# 1-Schematic_EspRosNodeCAN.net
KiCad netlist of a schematic drawn in EasyEDA
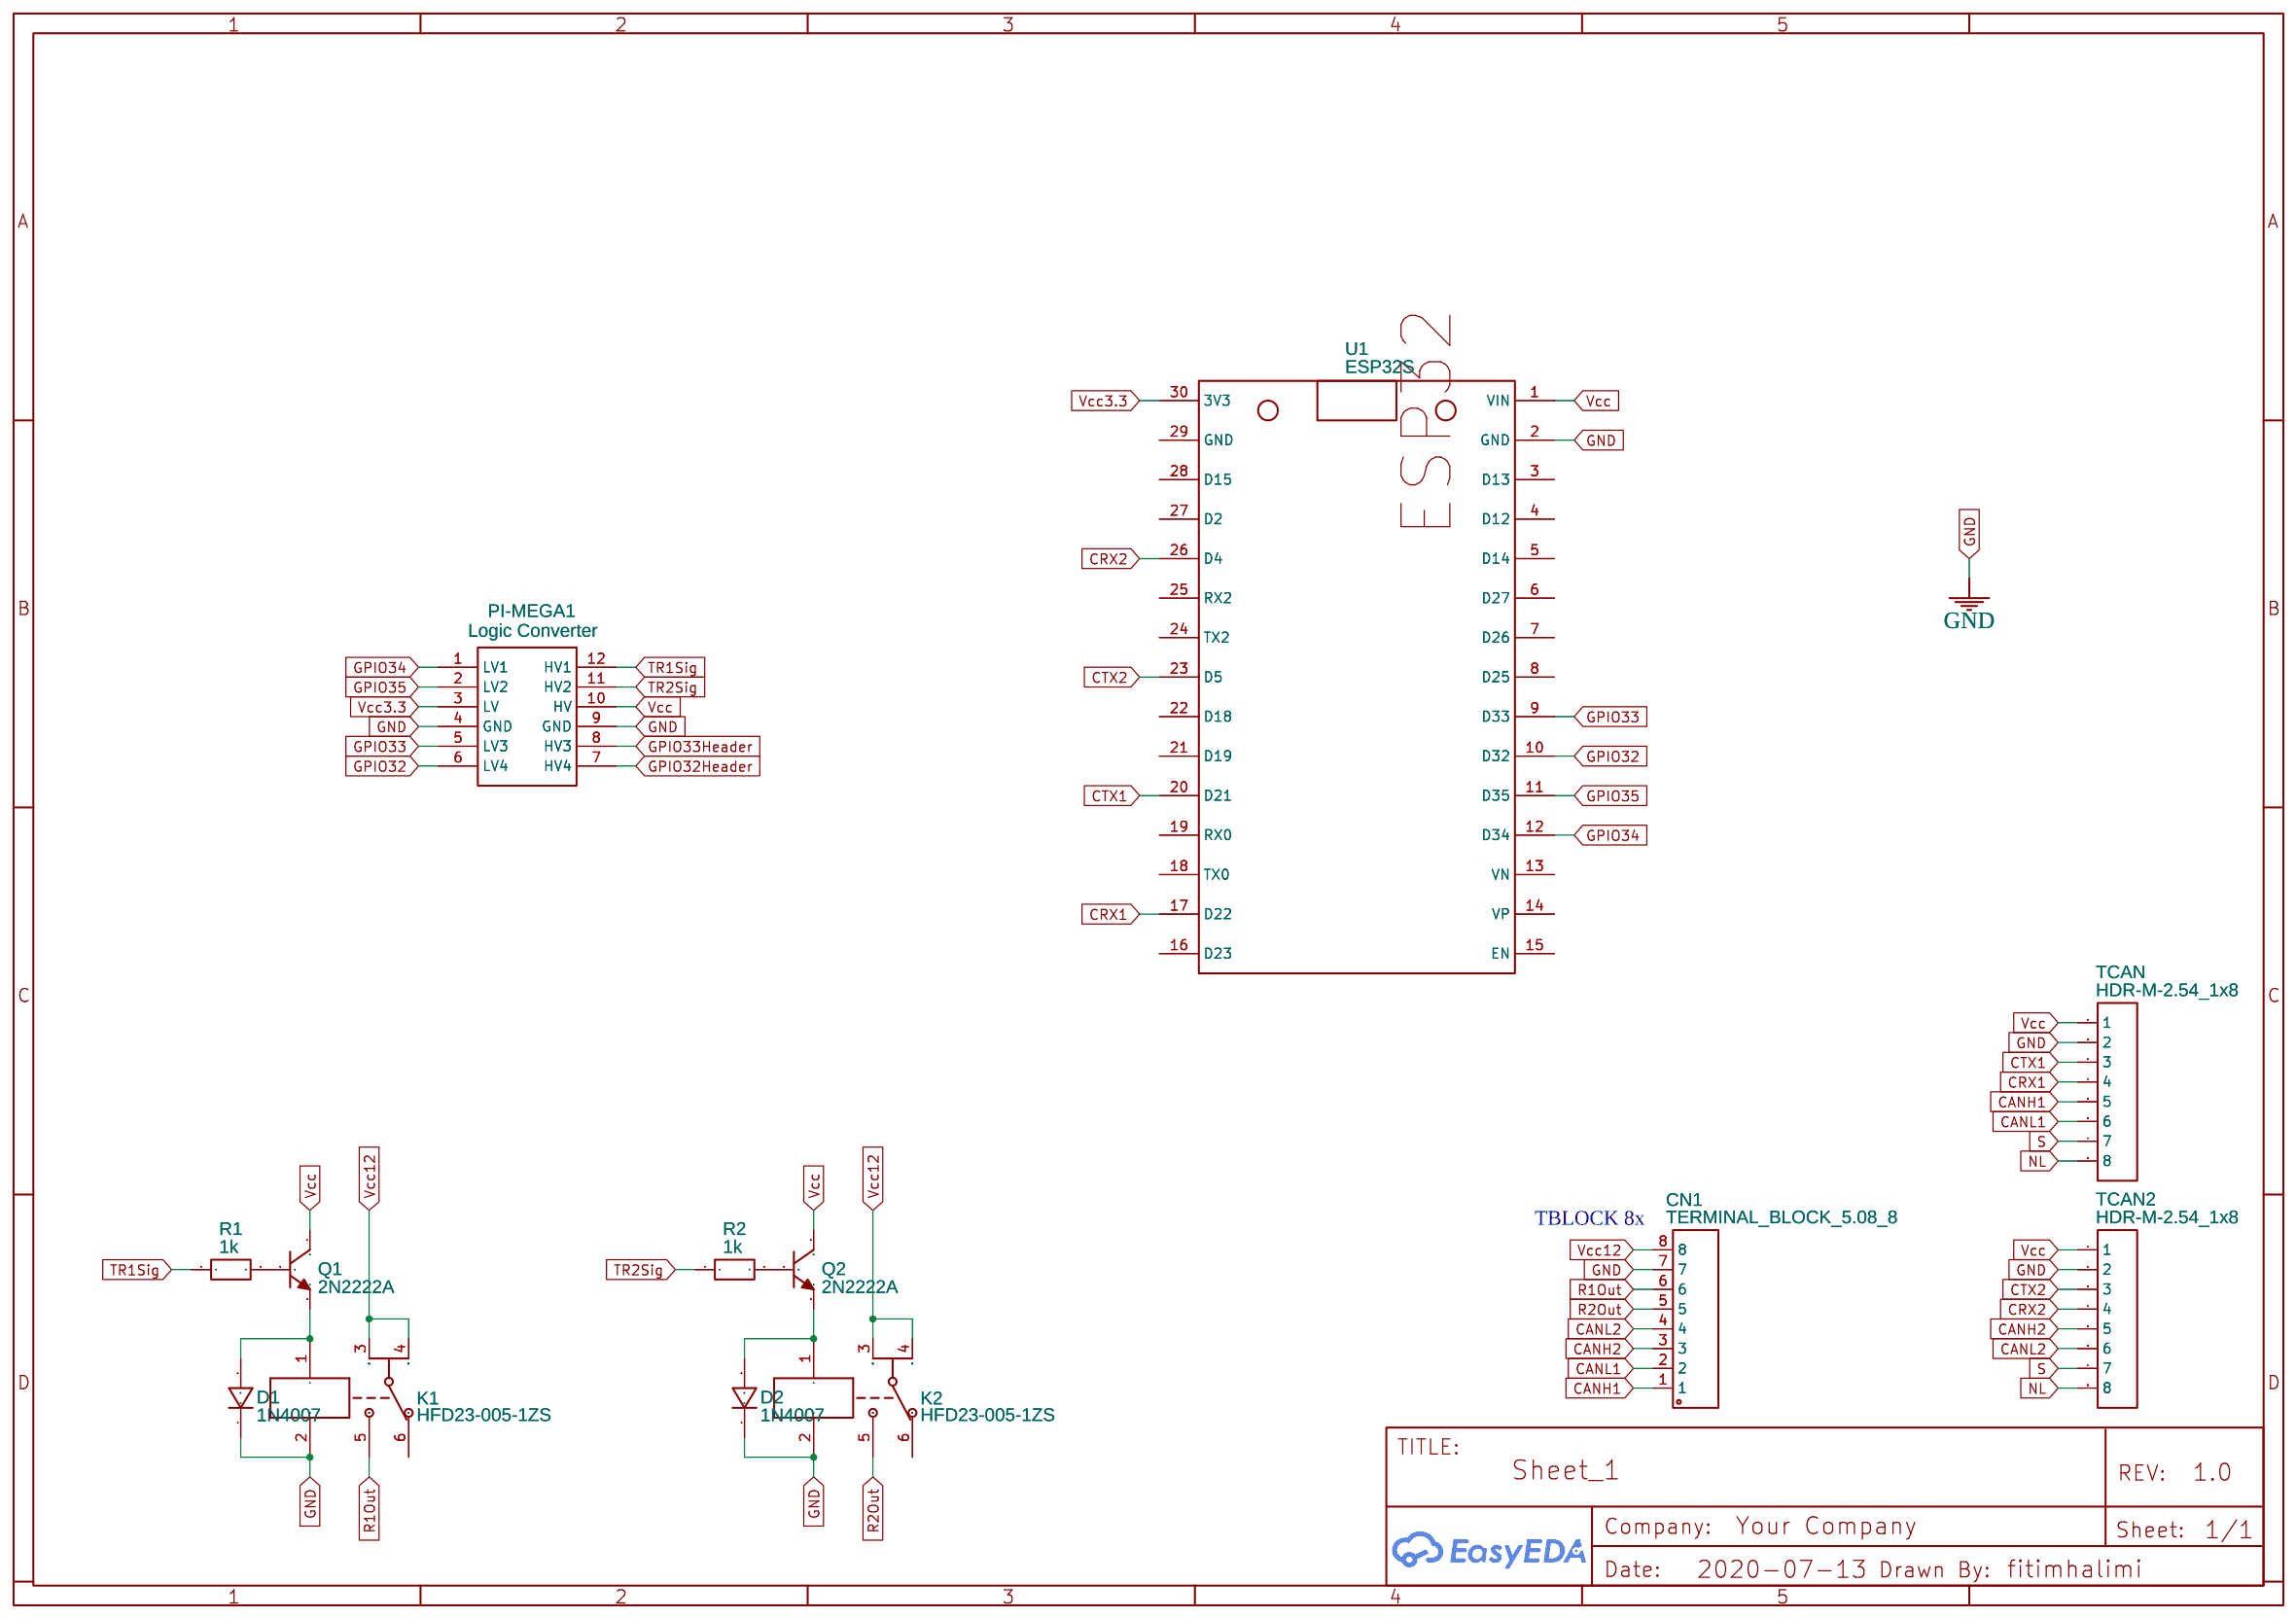
[diagram p0: schematic sheet]

(export (version "E")
  (design (tool "Eeschema 10.0.6"))
  (components
    (comp (ref "CN1") (value "TERMINAL_BLOCK_5.08_8") (libsource (lib "") (part "TERMINAL_BLOCK_5.08_8")))
    (comp (ref "D1")
      (value "1N4007")
      (fields (field (name "BOM_Supplier Part") "C106903"))
      (libsource (lib "") (part "1N4007"))
    )
    (comp (ref "D2")
      (value "1N4007")
      (fields (field (name "BOM_Supplier Part") "C106903"))
      (libsource (lib "") (part "1N4007"))
    )
    (comp (ref "K1")
      (value "HFD23-005-1ZS")
      (fields (field (name "BOM_Supplier Part") "C64002"))
      (libsource (lib "") (part "HFD23-005-1ZS"))
    )
    (comp (ref "K2")
      (value "HFD23-005-1ZS")
      (fields (field (name "BOM_Supplier Part") "C64002"))
      (libsource (lib "") (part "HFD23-005-1ZS"))
    )
    (comp (ref "PI-MEGA1")
      (value "Logic Converter")
      (fields (field (name "BOM_Manufacturer Part") "New SchematicLib"))
      (libsource (lib "") (part "4 Way Bi-Directional Logic Level Converter"))
    )
    (comp (ref "Q1")
      (value "2N2222A")
      (fields (field (name "BOM_Supplier Part") "C358533"))
      (libsource (lib "") (part "2N2222A"))
    )
    (comp (ref "Q2")
      (value "2N2222A")
      (fields (field (name "BOM_Supplier Part") "C358533"))
      (libsource (lib "") (part "2N2222A"))
    )
    (comp (ref "R1") (value "1k") (libsource (lib "") (part "R_AXIAL-0.4_EU")))
    (comp (ref "R2") (value "1k") (libsource (lib "") (part "R_AXIAL-0.4_EU")))
    (comp (ref "TCAN")
      (value "HDR-M-2.54_1x8")
      (fields (field (name "BOM_Supplier Part") "C190820"))
      (libsource (lib "") (part "HDR-M-2.54_1x8"))
    )
    (comp (ref "TCAN2")
      (value "HDR-M-2.54_1x8")
      (fields (field (name "BOM_Supplier Part") "C190820"))
      (libsource (lib "") (part "HDR-M-2.54_1x8"))
    )
    (comp (ref "U1")
      (value "ESP32S")
      (fields (field (name "BOM_Manufacturer Part") "New SchematicLib"))
      (libsource (lib "") (part "ESP32S"))
    )
  )
  (nets
    (net (code "1") (name "CANH1") (class "Default")
      (node (ref "CN1") (pin "1") (pinfunction "1_1") (pintype "unspecified"))
      (node (ref "TCAN") (pin "5") (pinfunction "5_5") (pintype "unspecified"))
    )
    (net (code "2") (name "CANH2") (class "Default")
      (node (ref "CN1") (pin "3") (pinfunction "3_3") (pintype "unspecified"))
      (node (ref "TCAN2") (pin "5") (pinfunction "5_5") (pintype "unspecified"))
    )
    (net (code "3") (name "CANL1") (class "Default")
      (node (ref "CN1") (pin "2") (pinfunction "2_2") (pintype "unspecified"))
      (node (ref "TCAN") (pin "6") (pinfunction "6_6") (pintype "unspecified"))
    )
    (net (code "4") (name "CANL2") (class "Default")
      (node (ref "CN1") (pin "4") (pinfunction "4_4") (pintype "unspecified"))
      (node (ref "TCAN2") (pin "6") (pinfunction "6_6") (pintype "unspecified"))
    )
    (net (code "5") (name "CRX1") (class "Default")
      (node (ref "TCAN") (pin "4") (pinfunction "4_4") (pintype "unspecified"))
      (node (ref "U1") (pin "17") (pinfunction "D22_17") (pintype "unspecified"))
    )
    (net (code "6") (name "CRX2") (class "Default")
      (node (ref "TCAN2") (pin "4") (pinfunction "4_4") (pintype "unspecified"))
      (node (ref "U1") (pin "26") (pinfunction "D4_26") (pintype "unspecified"))
    )
    (net (code "7") (name "CTX1") (class "Default")
      (node (ref "TCAN") (pin "3") (pinfunction "3_3") (pintype "unspecified"))
      (node (ref "U1") (pin "20") (pinfunction "D21_20") (pintype "unspecified"))
    )
    (net (code "8") (name "CTX2") (class "Default")
      (node (ref "TCAN2") (pin "3") (pinfunction "3_3") (pintype "unspecified"))
      (node (ref "U1") (pin "23") (pinfunction "D5_23") (pintype "unspecified"))
    )
    (net (code "9") (name "GND") (class "Default")
      (node (ref "CN1") (pin "7") (pinfunction "7_7") (pintype "unspecified"))
      (node (ref "D1") (pin "1") (pinfunction "1_1") (pintype "unspecified"))
      (node (ref "D2") (pin "1") (pinfunction "1_1") (pintype "unspecified"))
      (node (ref "K1") (pin "2") (pinfunction "2_2") (pintype "unspecified"))
      (node (ref "K2") (pin "2") (pinfunction "2_2") (pintype "unspecified"))
      (node (ref "PI-MEGA1") (pin "4") (pinfunction "GND_4") (pintype "unspecified"))
      (node (ref "PI-MEGA1") (pin "9") (pinfunction "GND_9") (pintype "unspecified"))
      (node (ref "TCAN") (pin "2") (pinfunction "2_2") (pintype "unspecified"))
      (node (ref "TCAN2") (pin "2") (pinfunction "2_2") (pintype "unspecified"))
      (node (ref "U1") (pin "2") (pinfunction "GND_2") (pintype "unspecified"))
    )
    (net (code "10") (name "GPIO32") (class "Default")
      (node (ref "PI-MEGA1") (pin "6") (pinfunction "LV4_6") (pintype "unspecified"))
      (node (ref "U1") (pin "10") (pinfunction "D32_10") (pintype "unspecified"))
    )
    (net (code "11") (name "GPIO32Header") (class "Default")
      (node (ref "PI-MEGA1") (pin "7") (pinfunction "HV4_7") (pintype "unspecified"))
    )
    (net (code "12") (name "GPIO33") (class "Default")
      (node (ref "PI-MEGA1") (pin "5") (pinfunction "LV3_5") (pintype "unspecified"))
      (node (ref "U1") (pin "9") (pinfunction "D33_9") (pintype "unspecified"))
    )
    (net (code "13") (name "GPIO33Header") (class "Default")
      (node (ref "PI-MEGA1") (pin "8") (pinfunction "HV3_8") (pintype "unspecified"))
    )
    (net (code "14") (name "GPIO34") (class "Default")
      (node (ref "PI-MEGA1") (pin "1") (pinfunction "LV1_1") (pintype "unspecified"))
      (node (ref "U1") (pin "12") (pinfunction "D34_12") (pintype "unspecified"))
    )
    (net (code "15") (name "GPIO35") (class "Default")
      (node (ref "PI-MEGA1") (pin "2") (pinfunction "LV2_2") (pintype "unspecified"))
      (node (ref "U1") (pin "11") (pinfunction "D35_11") (pintype "unspecified"))
    )
    (net (code "16") (name "NL") (class "Default")
      (node (ref "TCAN") (pin "8") (pinfunction "8_8") (pintype "unspecified"))
      (node (ref "TCAN2") (pin "8") (pinfunction "8_8") (pintype "unspecified"))
    )
    (net (code "17") (name "Net-(Q1-B)") (class "Default")
      (node (ref "Q1") (pin "2") (pinfunction "B_2") (pintype "unspecified"))
      (node (ref "R1") (pin "2") (pinfunction "2_2") (pintype "unspecified"))
    )
    (net (code "18") (name "Net-(Q1-E)") (class "Default")
      (node (ref "D1") (pin "2") (pinfunction "2_2") (pintype "unspecified"))
      (node (ref "K1") (pin "1") (pinfunction "1_1") (pintype "unspecified"))
      (node (ref "Q1") (pin "3") (pinfunction "E_3") (pintype "unspecified"))
    )
    (net (code "19") (name "Net-(Q2-B)") (class "Default")
      (node (ref "Q2") (pin "2") (pinfunction "B_2") (pintype "unspecified"))
      (node (ref "R2") (pin "2") (pinfunction "2_2") (pintype "unspecified"))
    )
    (net (code "20") (name "Net-(Q2-E)") (class "Default")
      (node (ref "D2") (pin "2") (pinfunction "2_2") (pintype "unspecified"))
      (node (ref "K2") (pin "1") (pinfunction "1_1") (pintype "unspecified"))
      (node (ref "Q2") (pin "3") (pinfunction "E_3") (pintype "unspecified"))
    )
    (net (code "21") (name "R1Out") (class "Default")
      (node (ref "CN1") (pin "6") (pinfunction "6_6") (pintype "unspecified"))
      (node (ref "K1") (pin "5") (pinfunction "NO_5") (pintype "unspecified"))
    )
    (net (code "22") (name "R2Out") (class "Default")
      (node (ref "CN1") (pin "5") (pinfunction "5_5") (pintype "unspecified"))
      (node (ref "K2") (pin "5") (pinfunction "NO_5") (pintype "unspecified"))
    )
    (net (code "23") (name "S") (class "Default")
      (node (ref "TCAN") (pin "7") (pinfunction "7_7") (pintype "unspecified"))
      (node (ref "TCAN2") (pin "7") (pinfunction "7_7") (pintype "unspecified"))
    )
    (net (code "24") (name "TR1Sig") (class "Default")
      (node (ref "PI-MEGA1") (pin "12") (pinfunction "HV1_12") (pintype "unspecified"))
      (node (ref "R1") (pin "1") (pinfunction "1_1") (pintype "unspecified"))
    )
    (net (code "25") (name "TR2Sig") (class "Default")
      (node (ref "PI-MEGA1") (pin "11") (pinfunction "HV2_11") (pintype "unspecified"))
      (node (ref "R2") (pin "1") (pinfunction "1_1") (pintype "unspecified"))
    )
    (net (code "26") (name "Vcc") (class "Default")
      (node (ref "PI-MEGA1") (pin "10") (pinfunction "HV_10") (pintype "unspecified"))
      (node (ref "Q1") (pin "1") (pinfunction "C_1") (pintype "unspecified"))
      (node (ref "Q2") (pin "1") (pinfunction "C_1") (pintype "unspecified"))
      (node (ref "TCAN") (pin "1") (pinfunction "1_1") (pintype "unspecified"))
      (node (ref "TCAN2") (pin "1") (pinfunction "1_1") (pintype "unspecified"))
      (node (ref "U1") (pin "1") (pinfunction "VIN_1") (pintype "unspecified"))
    )
    (net (code "27") (name "Vcc3.3") (class "Default")
      (node (ref "PI-MEGA1") (pin "3") (pinfunction "LV_3") (pintype "unspecified"))
      (node (ref "U1") (pin "30") (pinfunction "3V3_30") (pintype "unspecified"))
    )
    (net (code "28") (name "Vcc12") (class "Default")
      (node (ref "CN1") (pin "8") (pinfunction "8_8") (pintype "unspecified"))
      (node (ref "K1") (pin "3") (pinfunction "COM_3") (pintype "unspecified"))
      (node (ref "K1") (pin "4") (pinfunction "COM_4") (pintype "unspecified"))
      (node (ref "K2") (pin "3") (pinfunction "COM_3") (pintype "unspecified"))
      (node (ref "K2") (pin "4") (pinfunction "COM_4") (pintype "unspecified"))
    )
    (net (code "29") (name "unconnected-(K1-NC-Pad6)") (class "Default")
      (node (ref "K1") (pin "6") (pinfunction "NC_6") (pintype "unspecified"))
    )
    (net (code "30") (name "unconnected-(K2-NC-Pad6)") (class "Default")
      (node (ref "K2") (pin "6") (pinfunction "NC_6") (pintype "unspecified"))
    )
    (net (code "31") (name "unconnected-(U1-D2-Pad27)") (class "Default")
      (node (ref "U1") (pin "27") (pinfunction "D2_27") (pintype "unspecified"))
    )
    (net (code "32") (name "unconnected-(U1-D12-Pad4)") (class "Default")
      (node (ref "U1") (pin "4") (pinfunction "D12_4") (pintype "unspecified"))
    )
    (net (code "33") (name "unconnected-(U1-D13-Pad3)") (class "Default")
      (node (ref "U1") (pin "3") (pinfunction "D13_3") (pintype "unspecified"))
    )
    (net (code "34") (name "unconnected-(U1-D14-Pad5)") (class "Default")
      (node (ref "U1") (pin "5") (pinfunction "D14_5") (pintype "unspecified"))
    )
    (net (code "35") (name "unconnected-(U1-D15-Pad28)") (class "Default")
      (node (ref "U1") (pin "28") (pinfunction "D15_28") (pintype "unspecified"))
    )
    (net (code "36") (name "unconnected-(U1-D18-Pad22)") (class "Default")
      (node (ref "U1") (pin "22") (pinfunction "D18_22") (pintype "unspecified"))
    )
    (net (code "37") (name "unconnected-(U1-D19-Pad21)") (class "Default")
      (node (ref "U1") (pin "21") (pinfunction "D19_21") (pintype "unspecified"))
    )
    (net (code "38") (name "unconnected-(U1-D23-Pad16)") (class "Default")
      (node (ref "U1") (pin "16") (pinfunction "D23_16") (pintype "unspecified"))
    )
    (net (code "39") (name "unconnected-(U1-D25-Pad8)") (class "Default")
      (node (ref "U1") (pin "8") (pinfunction "D25_8") (pintype "unspecified"))
    )
    (net (code "40") (name "unconnected-(U1-D26-Pad7)") (class "Default")
      (node (ref "U1") (pin "7") (pinfunction "D26_7") (pintype "unspecified"))
    )
    (net (code "41") (name "unconnected-(U1-D27-Pad6)") (class "Default")
      (node (ref "U1") (pin "6") (pinfunction "D27_6") (pintype "unspecified"))
    )
    (net (code "42") (name "unconnected-(U1-EN-Pad15)") (class "Default")
      (node (ref "U1") (pin "15") (pinfunction "EN_15") (pintype "unspecified"))
    )
    (net (code "43") (name "unconnected-(U1-GND-Pad29)") (class "Default")
      (node (ref "U1") (pin "29") (pinfunction "GND_29") (pintype "unspecified"))
    )
    (net (code "44") (name "unconnected-(U1-RX0-Pad19)") (class "Default")
      (node (ref "U1") (pin "19") (pinfunction "RX0_19") (pintype "unspecified"))
    )
    (net (code "45") (name "unconnected-(U1-RX2-Pad25)") (class "Default")
      (node (ref "U1") (pin "25") (pinfunction "RX2_25") (pintype "unspecified"))
    )
    (net (code "46") (name "unconnected-(U1-TX0-Pad18)") (class "Default")
      (node (ref "U1") (pin "18") (pinfunction "TX0_18") (pintype "unspecified"))
    )
    (net (code "47") (name "unconnected-(U1-TX2-Pad24)") (class "Default")
      (node (ref "U1") (pin "24") (pinfunction "TX2_24") (pintype "unspecified"))
    )
    (net (code "48") (name "unconnected-(U1-VN-Pad13)") (class "Default")
      (node (ref "U1") (pin "13") (pinfunction "VN_13") (pintype "unspecified"))
    )
    (net (code "49") (name "unconnected-(U1-VP-Pad14)") (class "Default")
      (node (ref "U1") (pin "14") (pinfunction "VP_14") (pintype "unspecified"))
    )
  )
)
